# OUT.net
KiCad netlist of a schematic drawn in Altium Designer
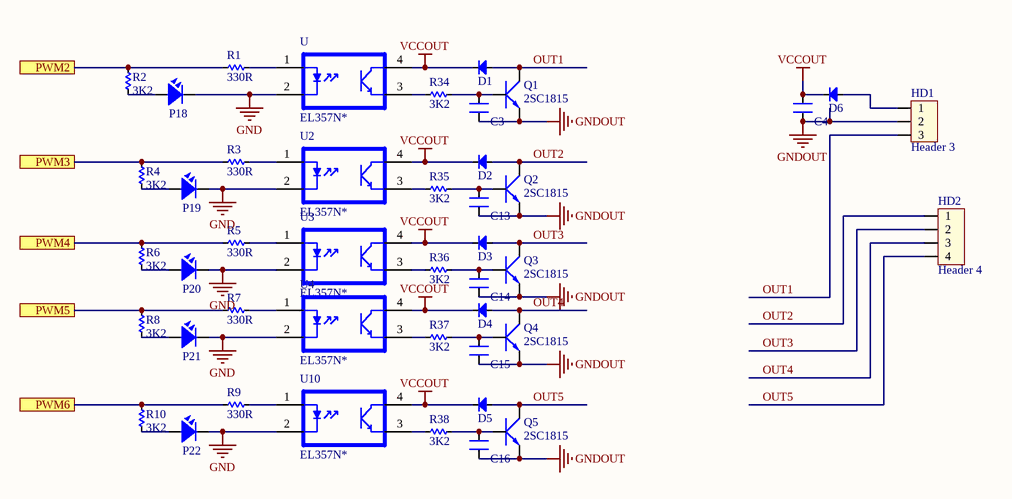
[diagram p0: OUT.SchDoc]

(export (version "E")
  (design (tool "Eeschema 10.0.6"))
  (components
    (comp (ref "C3") (value "100nF") (footprint "CN-SMD-0805") (libsource (lib "nhan") (part "CN")))
    (comp (ref "C4") (value "100nF") (footprint "CN-SMD-0805") (libsource (lib "nhan") (part "CN")))
    (comp (ref "C13") (value "100nF") (footprint "CN-SMD-0805") (libsource (lib "nhan") (part "CN")))
    (comp (ref "C14") (value "100nF") (footprint "CN-SMD-0805") (libsource (lib "nhan") (part "CN")))
    (comp (ref "C15") (value "100nF") (footprint "CN-SMD-0805") (libsource (lib "nhan") (part "CN")))
    (comp (ref "C16") (value "100nF") (footprint "CN-SMD-0805") (libsource (lib "nhan") (part "CN")))
    (comp (ref "D1")
      (value "Diode")
      (footprint "DIO-SMD-123")
      (description "Default Diode")
      (fields (field (name "PUBLISHER") "Altium Limited"))
      (libsource (lib "nhan") (part "Diode"))
    )
    (comp (ref "D2")
      (value "Diode")
      (footprint "DIO-SMD-123")
      (description "Default Diode")
      (fields (field (name "PUBLISHER") "Altium Limited"))
      (libsource (lib "nhan") (part "Diode"))
    )
    (comp (ref "D3")
      (value "Diode")
      (footprint "DIO-SMD-123")
      (description "Default Diode")
      (fields (field (name "PUBLISHER") "Altium Limited"))
      (libsource (lib "nhan") (part "Diode"))
    )
    (comp (ref "D4")
      (value "Diode")
      (footprint "DIO-SMD-123")
      (description "Default Diode")
      (fields (field (name "PUBLISHER") "Altium Limited"))
      (libsource (lib "nhan") (part "Diode"))
    )
    (comp (ref "D5")
      (value "Diode")
      (footprint "DIO-SMD-123")
      (description "Default Diode")
      (fields (field (name "PUBLISHER") "Altium Limited"))
      (libsource (lib "nhan") (part "Diode"))
    )
    (comp (ref "D6")
      (value "Diode")
      (footprint "DIO-SMD-123")
      (description "Default Diode")
      (fields (field (name "PUBLISHER") "Altium Limited"))
      (libsource (lib "nhan") (part "Diode"))
    )
    (comp (ref "HD1")
      (value "Header 3")
      (footprint "HED3T")
      (description "Header 3 (Green)")
      (libsource (lib "syhaunguyen") (part "Hed3"))
    )
    (comp (ref "HD2")
      (value "Header 4")
      (footprint "HED4T")
      (description "Header 4 (Green)")
      (libsource (lib "syhaunguyen") (part "Hed4"))
    )
    (comp (ref "P18")
      (value "LED")
      (footprint "LED-0805-Green")
      (libsource (lib "BanLinhKien") (part "LED SMD"))
    )
    (comp (ref "P19")
      (value "LED")
      (footprint "LED-0805-Green")
      (libsource (lib "BanLinhKien") (part "LED SMD"))
    )
    (comp (ref "P20")
      (value "LED")
      (footprint "LED-0805-Green")
      (libsource (lib "BanLinhKien") (part "LED SMD"))
    )
    (comp (ref "P21")
      (value "LED")
      (footprint "LED-0805-Green")
      (libsource (lib "BanLinhKien") (part "LED SMD"))
    )
    (comp (ref "P22")
      (value "LED")
      (footprint "LED-0805-Green")
      (libsource (lib "BanLinhKien") (part "LED SMD"))
    )
    (comp (ref "Q1")
      (value "2SC1815")
      (footprint "SOT23-321")
      (description "NPN 600mW, ECB")
      (libsource (lib "TechMT.VN_Lib_Project v2") (part "2SC1815"))
    )
    (comp (ref "Q2")
      (value "2SC1815")
      (footprint "SOT23-321")
      (description "NPN 600mW, ECB")
      (libsource (lib "TechMT.VN_Lib_Project v2") (part "2SC1815"))
    )
    (comp (ref "Q3")
      (value "2SC1815")
      (footprint "SOT23-321")
      (description "NPN 600mW, ECB")
      (libsource (lib "TechMT.VN_Lib_Project v2") (part "2SC1815"))
    )
    (comp (ref "Q4")
      (value "2SC1815")
      (footprint "SOT23-321")
      (description "NPN 600mW, ECB")
      (libsource (lib "TechMT.VN_Lib_Project v2") (part "2SC1815"))
    )
    (comp (ref "Q5")
      (value "2SC1815")
      (footprint "SOT23-321")
      (description "NPN 600mW, ECB")
      (libsource (lib "TechMT.VN_Lib_Project v2") (part "2SC1815"))
    )
    (comp (ref "R1") (value "330R") (footprint "RES-SMD-0805") (libsource (lib "nhan") (part "R")))
    (comp (ref "R2") (value "3K2") (footprint "RES-SMD-0805") (libsource (lib "nhan") (part "R")))
    (comp (ref "R3") (value "330R") (footprint "RES-SMD-0805") (libsource (lib "nhan") (part "R")))
    (comp (ref "R4") (value "3K2") (footprint "RES-SMD-0805") (libsource (lib "nhan") (part "R")))
    (comp (ref "R5") (value "330R") (footprint "RES-SMD-0805") (libsource (lib "nhan") (part "R")))
    (comp (ref "R6") (value "3K2") (footprint "RES-SMD-0805") (libsource (lib "nhan") (part "R")))
    (comp (ref "R7") (value "330R") (footprint "RES-SMD-0805") (libsource (lib "nhan") (part "R")))
    (comp (ref "R8") (value "3K2") (footprint "RES-SMD-0805") (libsource (lib "nhan") (part "R")))
    (comp (ref "R9") (value "330R") (footprint "RES-SMD-0805") (libsource (lib "nhan") (part "R")))
    (comp (ref "R10") (value "3K2") (footprint "RES-SMD-0805") (libsource (lib "nhan") (part "R")))
    (comp (ref "R34") (value "3K2") (footprint "RES-SMD-0805") (libsource (lib "nhan") (part "R")))
    (comp (ref "R35") (value "3K2") (footprint "RES-SMD-0805") (libsource (lib "nhan") (part "R")))
    (comp (ref "R36") (value "3K2") (footprint "RES-SMD-0805") (libsource (lib "nhan") (part "R")))
    (comp (ref "R37") (value "3K2") (footprint "RES-SMD-0805") (libsource (lib "nhan") (part "R")))
    (comp (ref "R38") (value "3K2") (footprint "RES-SMD-0805") (libsource (lib "nhan") (part "R")))
    (comp (ref "U")
      (value "EL357N*")
      (footprint "SOP4N")
      (description "Optoisolator Transistor Output 3750Vrms 1 Channel 4-SOP _2.54mm_")
      (fields (field (name "MP") "EL357N_A__TA_-G") (field (name "MF") "Everlight Electronics"))
      (libsource (lib "nhan") (part "EL357N(A)(TA)-G"))
    )
    (comp (ref "U2")
      (value "EL357N*")
      (footprint "SOP4N")
      (description "Optoisolator Transistor Output 3750Vrms 1 Channel 4-SOP _2.54mm_")
      (fields (field (name "MP") "EL357N_A__TA_-G") (field (name "MF") "Everlight Electronics"))
      (libsource (lib "nhan") (part "EL357N(A)(TA)-G"))
    )
    (comp (ref "U3")
      (value "EL357N*")
      (footprint "SOP4N")
      (description "Optoisolator Transistor Output 3750Vrms 1 Channel 4-SOP _2.54mm_")
      (fields (field (name "MP") "EL357N_A__TA_-G") (field (name "MF") "Everlight Electronics"))
      (libsource (lib "nhan") (part "EL357N(A)(TA)-G"))
    )
    (comp (ref "U4")
      (value "EL357N*")
      (footprint "SOP4N")
      (description "Optoisolator Transistor Output 3750Vrms 1 Channel 4-SOP _2.54mm_")
      (fields (field (name "MP") "EL357N_A__TA_-G") (field (name "MF") "Everlight Electronics"))
      (libsource (lib "nhan") (part "EL357N(A)(TA)-G"))
    )
    (comp (ref "U10")
      (value "EL357N*")
      (footprint "SOP4N")
      (description "Optoisolator Transistor Output 3750Vrms 1 Channel 4-SOP _2.54mm_")
      (fields (field (name "MP") "EL357N_A__TA_-G") (field (name "MF") "Everlight Electronics"))
      (libsource (lib "nhan") (part "EL357N(A)(TA)-G"))
    )
  )
  (nets
    (net (code "1") (name "/OUT1") (class "Default")
      (node (ref "D1") (pin "1") (pinfunction "A_1") (pintype "passive"))
      (node (ref "HD1") (pin "3") (pinfunction "3_3") (pintype "passive"))
      (node (ref "Q1") (pin "2") (pinfunction "C_2") (pintype "passive"))
    )
    (net (code "2") (name "/OUT2") (class "Default")
      (node (ref "D2") (pin "1") (pinfunction "A_1") (pintype "passive"))
      (node (ref "HD2") (pin "1") (pinfunction "1_1") (pintype "passive"))
      (node (ref "Q2") (pin "2") (pinfunction "C_2") (pintype "passive"))
    )
    (net (code "3") (name "/OUT3") (class "Default")
      (node (ref "D3") (pin "1") (pinfunction "A_1") (pintype "passive"))
      (node (ref "HD2") (pin "2") (pinfunction "2_2") (pintype "passive"))
      (node (ref "Q3") (pin "2") (pinfunction "C_2") (pintype "passive"))
    )
    (net (code "4") (name "/OUT4") (class "Default")
      (node (ref "D4") (pin "1") (pinfunction "A_1") (pintype "passive"))
      (node (ref "HD2") (pin "3") (pinfunction "3_3") (pintype "passive"))
      (node (ref "Q4") (pin "2") (pinfunction "C_2") (pintype "passive"))
    )
    (net (code "5") (name "/OUT5") (class "Default")
      (node (ref "D5") (pin "1") (pinfunction "A_1") (pintype "passive"))
      (node (ref "HD2") (pin "4") (pinfunction "4_4") (pintype "passive"))
      (node (ref "Q5") (pin "2") (pinfunction "C_2") (pintype "passive"))
    )
    (net (code "6") (name "/PWM2") (class "Default")
      (node (ref "R1") (pin "1") (pinfunction "1_1") (pintype "passive"))
      (node (ref "R2") (pin "1") (pinfunction "1_1") (pintype "passive"))
    )
    (net (code "7") (name "/PWM3") (class "Default")
      (node (ref "R3") (pin "1") (pinfunction "1_1") (pintype "passive"))
      (node (ref "R4") (pin "1") (pinfunction "1_1") (pintype "passive"))
    )
    (net (code "8") (name "/PWM4") (class "Default")
      (node (ref "R5") (pin "1") (pinfunction "1_1") (pintype "passive"))
      (node (ref "R6") (pin "1") (pinfunction "1_1") (pintype "passive"))
    )
    (net (code "9") (name "/PWM5") (class "Default")
      (node (ref "R7") (pin "1") (pinfunction "1_1") (pintype "passive"))
      (node (ref "R8") (pin "1") (pinfunction "1_1") (pintype "passive"))
    )
    (net (code "10") (name "/PWM6") (class "Default")
      (node (ref "R10") (pin "1") (pinfunction "1_1") (pintype "passive"))
      (node (ref "R9") (pin "1") (pinfunction "1_1") (pintype "passive"))
    )
    (net (code "11") (name "GND") (class "Default")
      (node (ref "P18") (pin "2") (pinfunction "2_2") (pintype "passive"))
      (node (ref "P19") (pin "2") (pinfunction "2_2") (pintype "passive"))
      (node (ref "P20") (pin "2") (pinfunction "2_2") (pintype "passive"))
      (node (ref "P21") (pin "2") (pinfunction "2_2") (pintype "passive"))
      (node (ref "P22") (pin "2") (pinfunction "2_2") (pintype "passive"))
      (node (ref "U") (pin "2") (pinfunction "K_2") (pintype "passive"))
      (node (ref "U10") (pin "2") (pinfunction "K_2") (pintype "passive"))
      (node (ref "U2") (pin "2") (pinfunction "K_2") (pintype "passive"))
      (node (ref "U3") (pin "2") (pinfunction "K_2") (pintype "passive"))
      (node (ref "U4") (pin "2") (pinfunction "K_2") (pintype "passive"))
    )
    (net (code "12") (name "GNDOUT") (class "Default")
      (node (ref "C13") (pin "2") (pinfunction "2_2") (pintype "passive"))
      (node (ref "C14") (pin "2") (pinfunction "2_2") (pintype "passive"))
      (node (ref "C15") (pin "2") (pinfunction "2_2") (pintype "passive"))
      (node (ref "C16") (pin "2") (pinfunction "2_2") (pintype "passive"))
      (node (ref "C3") (pin "2") (pinfunction "2_2") (pintype "passive"))
      (node (ref "C4") (pin "2") (pinfunction "2_2") (pintype "passive"))
      (node (ref "HD1") (pin "2") (pinfunction "2_2") (pintype "passive"))
      (node (ref "Q1") (pin "1") (pinfunction "E_1") (pintype "passive"))
      (node (ref "Q2") (pin "1") (pinfunction "E_1") (pintype "passive"))
      (node (ref "Q3") (pin "1") (pinfunction "E_1") (pintype "passive"))
      (node (ref "Q4") (pin "1") (pinfunction "E_1") (pintype "passive"))
      (node (ref "Q5") (pin "1") (pinfunction "E_1") (pintype "passive"))
    )
    (net (code "13") (name "Net-(D6-A)") (class "Default")
      (node (ref "D6") (pin "1") (pinfunction "A_1") (pintype "passive"))
      (node (ref "HD1") (pin "1") (pinfunction "1_1") (pintype "passive"))
    )
    (net (code "14") (name "Net-(P18-Pad1)") (class "Default")
      (node (ref "P18") (pin "1") (pinfunction "1_1") (pintype "passive"))
      (node (ref "R2") (pin "2") (pinfunction "2_2") (pintype "passive"))
    )
    (net (code "15") (name "Net-(P19-Pad1)") (class "Default")
      (node (ref "P19") (pin "1") (pinfunction "1_1") (pintype "passive"))
      (node (ref "R4") (pin "2") (pinfunction "2_2") (pintype "passive"))
    )
    (net (code "16") (name "Net-(P20-Pad1)") (class "Default")
      (node (ref "P20") (pin "1") (pinfunction "1_1") (pintype "passive"))
      (node (ref "R6") (pin "2") (pinfunction "2_2") (pintype "passive"))
    )
    (net (code "17") (name "Net-(P21-Pad1)") (class "Default")
      (node (ref "P21") (pin "1") (pinfunction "1_1") (pintype "passive"))
      (node (ref "R8") (pin "2") (pinfunction "2_2") (pintype "passive"))
    )
    (net (code "18") (name "Net-(P22-Pad1)") (class "Default")
      (node (ref "P22") (pin "1") (pinfunction "1_1") (pintype "passive"))
      (node (ref "R10") (pin "2") (pinfunction "2_2") (pintype "passive"))
    )
    (net (code "19") (name "Net-(Q1-B)") (class "Default")
      (node (ref "C3") (pin "1") (pinfunction "1_1") (pintype "passive"))
      (node (ref "Q1") (pin "3") (pinfunction "B_3") (pintype "passive"))
      (node (ref "R34") (pin "2") (pinfunction "2_2") (pintype "passive"))
    )
    (net (code "20") (name "Net-(Q2-B)") (class "Default")
      (node (ref "C13") (pin "1") (pinfunction "1_1") (pintype "passive"))
      (node (ref "Q2") (pin "3") (pinfunction "B_3") (pintype "passive"))
      (node (ref "R35") (pin "2") (pinfunction "2_2") (pintype "passive"))
    )
    (net (code "21") (name "Net-(Q3-B)") (class "Default")
      (node (ref "C14") (pin "1") (pinfunction "1_1") (pintype "passive"))
      (node (ref "Q3") (pin "3") (pinfunction "B_3") (pintype "passive"))
      (node (ref "R36") (pin "2") (pinfunction "2_2") (pintype "passive"))
    )
    (net (code "22") (name "Net-(Q4-B)") (class "Default")
      (node (ref "C15") (pin "1") (pinfunction "1_1") (pintype "passive"))
      (node (ref "Q4") (pin "3") (pinfunction "B_3") (pintype "passive"))
      (node (ref "R37") (pin "2") (pinfunction "2_2") (pintype "passive"))
    )
    (net (code "23") (name "Net-(Q5-B)") (class "Default")
      (node (ref "C16") (pin "1") (pinfunction "1_1") (pintype "passive"))
      (node (ref "Q5") (pin "3") (pinfunction "B_3") (pintype "passive"))
      (node (ref "R38") (pin "2") (pinfunction "2_2") (pintype "passive"))
    )
    (net (code "24") (name "Net-(U-A)") (class "Default")
      (node (ref "R1") (pin "2") (pinfunction "2_2") (pintype "passive"))
      (node (ref "U") (pin "1") (pinfunction "A_1") (pintype "passive"))
    )
    (net (code "25") (name "Net-(U-E)") (class "Default")
      (node (ref "R34") (pin "1") (pinfunction "1_1") (pintype "passive"))
      (node (ref "U") (pin "3") (pinfunction "E_3") (pintype "passive"))
    )
    (net (code "26") (name "Net-(U2-A)") (class "Default")
      (node (ref "R3") (pin "2") (pinfunction "2_2") (pintype "passive"))
      (node (ref "U2") (pin "1") (pinfunction "A_1") (pintype "passive"))
    )
    (net (code "27") (name "Net-(U2-E)") (class "Default")
      (node (ref "R35") (pin "1") (pinfunction "1_1") (pintype "passive"))
      (node (ref "U2") (pin "3") (pinfunction "E_3") (pintype "passive"))
    )
    (net (code "28") (name "Net-(U3-A)") (class "Default")
      (node (ref "R5") (pin "2") (pinfunction "2_2") (pintype "passive"))
      (node (ref "U3") (pin "1") (pinfunction "A_1") (pintype "passive"))
    )
    (net (code "29") (name "Net-(U3-E)") (class "Default")
      (node (ref "R36") (pin "1") (pinfunction "1_1") (pintype "passive"))
      (node (ref "U3") (pin "3") (pinfunction "E_3") (pintype "passive"))
    )
    (net (code "30") (name "Net-(U4-A)") (class "Default")
      (node (ref "R7") (pin "2") (pinfunction "2_2") (pintype "passive"))
      (node (ref "U4") (pin "1") (pinfunction "A_1") (pintype "passive"))
    )
    (net (code "31") (name "Net-(U4-E)") (class "Default")
      (node (ref "R37") (pin "1") (pinfunction "1_1") (pintype "passive"))
      (node (ref "U4") (pin "3") (pinfunction "E_3") (pintype "passive"))
    )
    (net (code "32") (name "Net-(U10-A)") (class "Default")
      (node (ref "R9") (pin "2") (pinfunction "2_2") (pintype "passive"))
      (node (ref "U10") (pin "1") (pinfunction "A_1") (pintype "passive"))
    )
    (net (code "33") (name "Net-(U10-E)") (class "Default")
      (node (ref "R38") (pin "1") (pinfunction "1_1") (pintype "passive"))
      (node (ref "U10") (pin "3") (pinfunction "E_3") (pintype "passive"))
    )
    (net (code "34") (name "VCCOUT") (class "Default")
      (node (ref "C4") (pin "1") (pinfunction "1_1") (pintype "passive"))
      (node (ref "D1") (pin "2") (pinfunction "K_2") (pintype "passive"))
      (node (ref "D2") (pin "2") (pinfunction "K_2") (pintype "passive"))
      (node (ref "D3") (pin "2") (pinfunction "K_2") (pintype "passive"))
      (node (ref "D4") (pin "2") (pinfunction "K_2") (pintype "passive"))
      (node (ref "D5") (pin "2") (pinfunction "K_2") (pintype "passive"))
      (node (ref "D6") (pin "2") (pinfunction "K_2") (pintype "passive"))
      (node (ref "U") (pin "4") (pinfunction "C_4") (pintype "passive"))
      (node (ref "U10") (pin "4") (pinfunction "C_4") (pintype "passive"))
      (node (ref "U2") (pin "4") (pinfunction "C_4") (pintype "passive"))
      (node (ref "U3") (pin "4") (pinfunction "C_4") (pintype "passive"))
      (node (ref "U4") (pin "4") (pinfunction "C_4") (pintype "passive"))
    )
  )
)
